# control_board.net
KiCad netlist of a schematic drawn in EAGLE
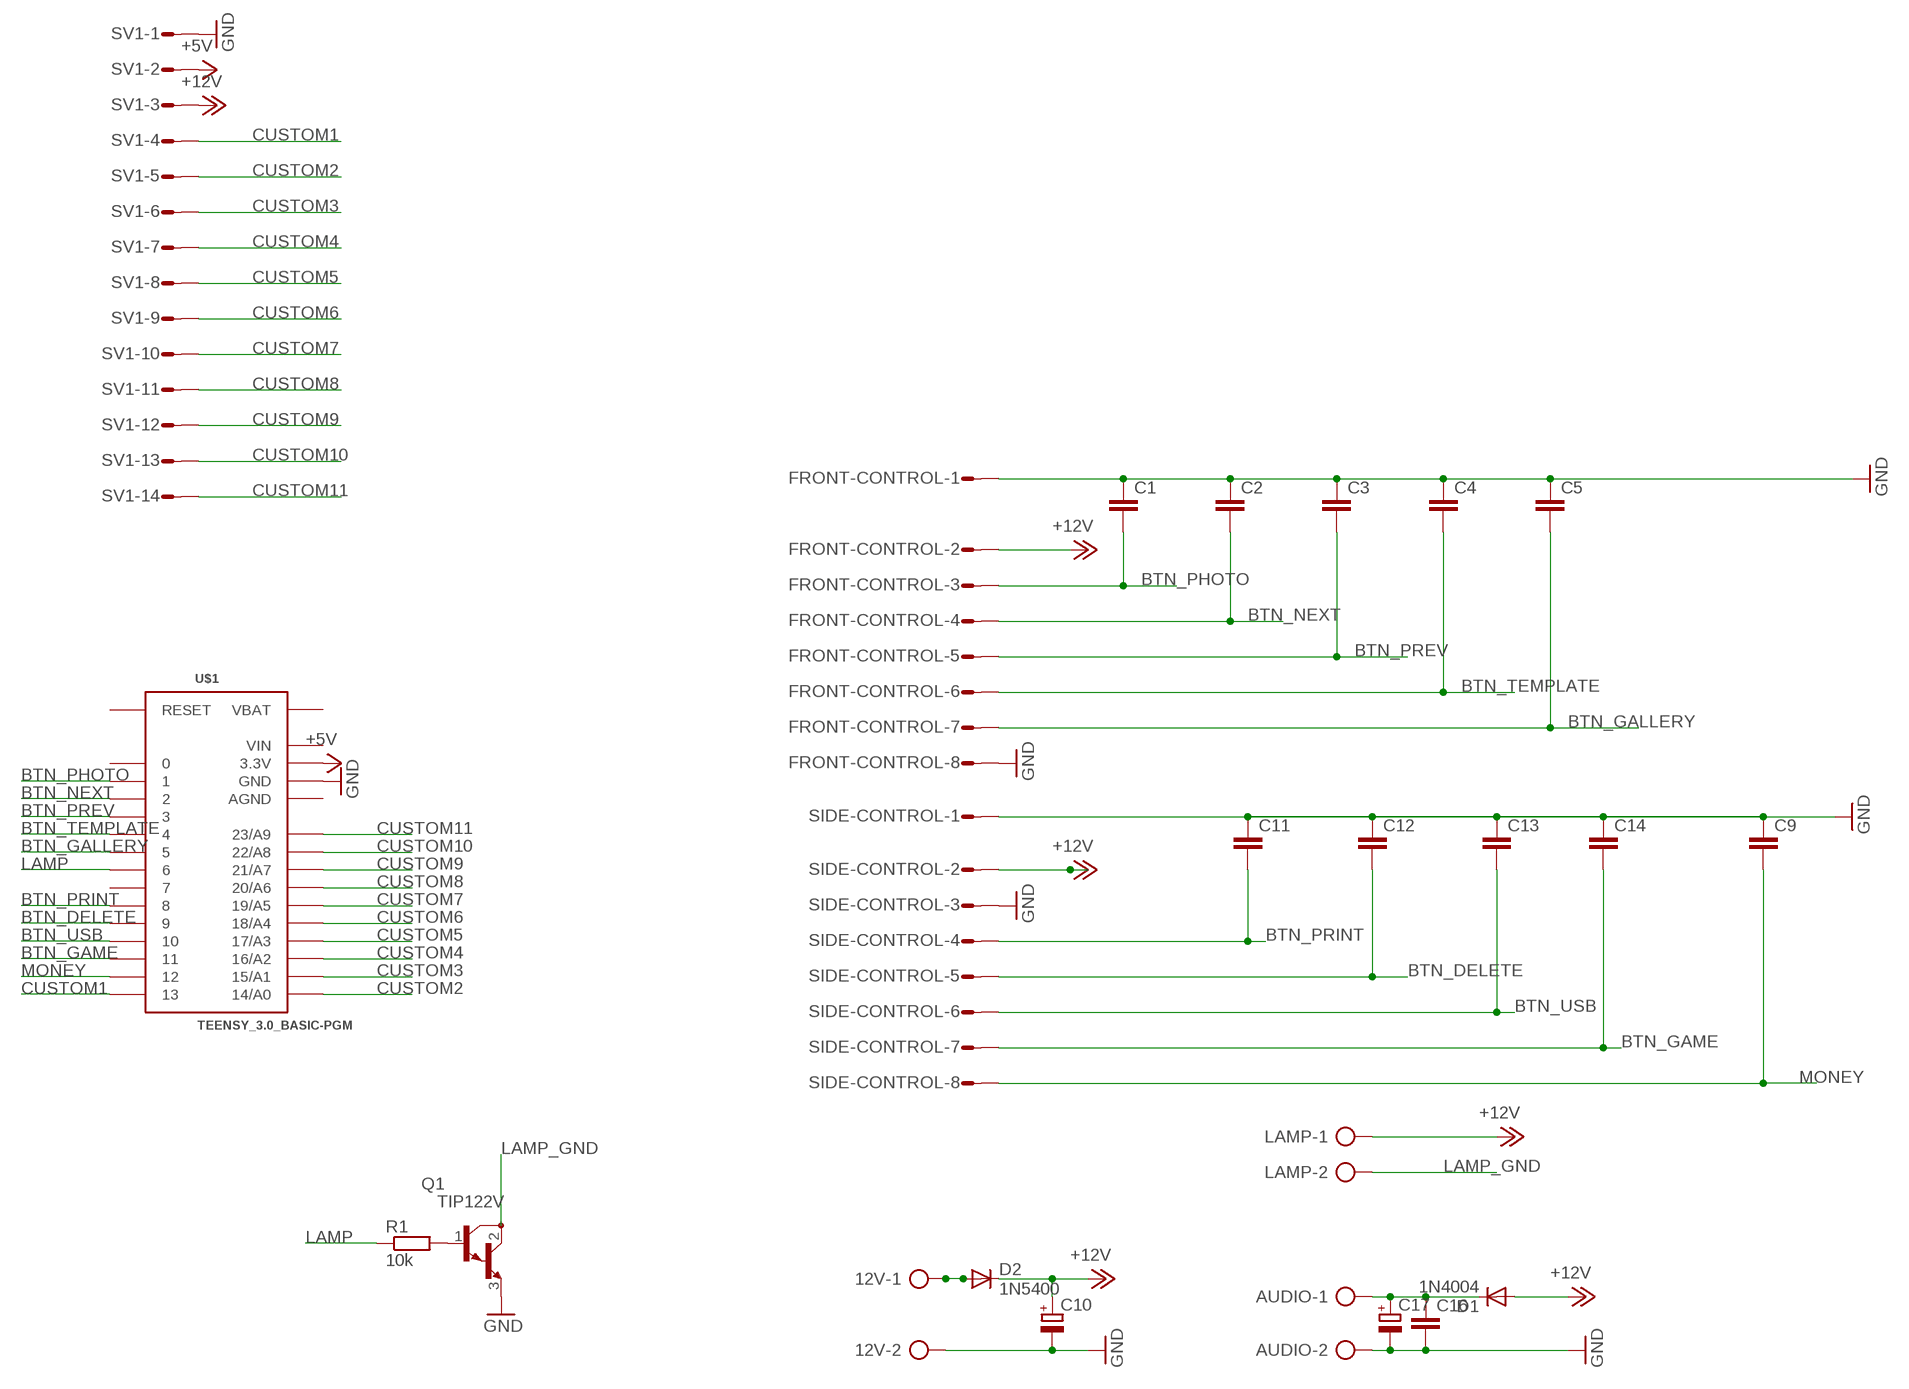
[diagram p0: schematic, sheet 1]

(export (version "E")
  (design (tool "Eeschema 10.0.6"))
  (components
    (comp (ref "12V")
      (value "AK300/2")
      (footprint "eagle-import:AK300_2")
      (libsource (lib "eagle-import") (part "AK300/2"))
    )
    (comp (ref "AUDIO")
      (value "AK300/2")
      (footprint "eagle-import:AK300_2")
      (libsource (lib "eagle-import") (part "AK300/2"))
    )
    (comp (ref "C1")
      (value "C-EU025-025X050")
      (footprint "eagle-import:C025-025X050")
      (libsource (lib "eagle-import") (part "resistor_C-EU025-025X050"))
    )
    (comp (ref "C2")
      (value "C-EU025-025X050")
      (footprint "eagle-import:C025-025X050")
      (libsource (lib "eagle-import") (part "resistor_C-EU025-025X050"))
    )
    (comp (ref "C3")
      (value "C-EU025-025X050")
      (footprint "eagle-import:C025-025X050")
      (libsource (lib "eagle-import") (part "resistor_C-EU025-025X050"))
    )
    (comp (ref "C4")
      (value "C-EU025-025X050")
      (footprint "eagle-import:C025-025X050")
      (libsource (lib "eagle-import") (part "resistor_C-EU025-025X050"))
    )
    (comp (ref "C5")
      (value "C-EU025-025X050")
      (footprint "eagle-import:C025-025X050")
      (libsource (lib "eagle-import") (part "resistor_C-EU025-025X050"))
    )
    (comp (ref "C9")
      (value "C-EU025-025X050")
      (footprint "eagle-import:C025-025X050")
      (libsource (lib "eagle-import") (part "C-EU025-025X050"))
    )
    (comp (ref "C10")
      (value "CPOL-EUE5-8.5")
      (footprint "eagle-import:E5-8,5")
      (libsource (lib "eagle-import") (part "CPOL-EUE5-8.5"))
    )
    (comp (ref "C11")
      (value "C-EU025-025X050")
      (footprint "eagle-import:C025-025X050")
      (libsource (lib "eagle-import") (part "C-EU025-025X050"))
    )
    (comp (ref "C12")
      (value "C-EU025-025X050")
      (footprint "eagle-import:C025-025X050")
      (libsource (lib "eagle-import") (part "C-EU025-025X050"))
    )
    (comp (ref "C13")
      (value "C-EU025-025X050")
      (footprint "eagle-import:C025-025X050")
      (libsource (lib "eagle-import") (part "C-EU025-025X050"))
    )
    (comp (ref "C14")
      (value "C-EU025-025X050")
      (footprint "eagle-import:C025-025X050")
      (libsource (lib "eagle-import") (part "C-EU025-025X050"))
    )
    (comp (ref "C16")
      (value "C-EU025-025X050")
      (footprint "eagle-import:C025-025X050")
      (libsource (lib "eagle-import") (part "C-EU025-025X050"))
    )
    (comp (ref "C17")
      (value "CPOL-EUE5-5")
      (footprint "eagle-import:E5-5")
      (libsource (lib "eagle-import") (part "CPOL-EUE5-5"))
    )
    (comp (ref "D1")
      (value "1N4004")
      (footprint "eagle-import:DO41-10")
      (libsource (lib "eagle-import") (part "1N4004"))
    )
    (comp (ref "D2")
      (value "1N5400")
      (footprint "eagle-import:DO201-15")
      (libsource (lib "eagle-import") (part "1N5400"))
    )
    (comp (ref "FRONT-CONTROL")
      (value "S08P")
      (footprint "eagle-import:S08P")
      (libsource (lib "eagle-import") (part "S08P"))
    )
    (comp (ref "LAMP")
      (value "AK300/2")
      (footprint "eagle-import:AK300_2")
      (libsource (lib "eagle-import") (part "AK300/2"))
    )
    (comp (ref "Q1")
      (value "TIP122V")
      (footprint "eagle-import:TO220V")
      (libsource (lib "eagle-import") (part "TIP122V"))
    )
    (comp (ref "R1")
      (value "10k")
      (footprint "eagle-import:0204_7")
      (libsource (lib "eagle-import") (part "R-EU_0204/7"))
    )
    (comp (ref "SIDE-CONTROL")
      (value "S08P")
      (footprint "eagle-import:S08P")
      (libsource (lib "eagle-import") (part "S08P"))
    )
    (comp (ref "SV1")
      (value "S14P")
      (footprint "eagle-import:S14P")
      (libsource (lib "eagle-import") (part "S14P"))
    )
    (comp (ref "U$1")
      (value "TEENSY_3.0_BASIC-PGM")
      (footprint "eagle-import:TEENSY_3.0_BASIC-PGM")
      (libsource (lib "eagle-import") (part "TEENSY_3.0_BASIC-PGM"))
    )
  )
  (nets
    (net (code "1") (name "+5V") (class "Default")
      (node (ref "SV1") (pin "2") (pinfunction "S_2") (pintype "passive"))
      (node (ref "U$1") (pin "3.3V") (pinfunction "3.3V_3.3V") (pintype "power_in"))
      (node (ref "U$1") (pin "3.3V1") (pinfunction "3.3V_3.3V1") (pintype "power_in"))
    )
    (net (code "2") (name "+12V") (class "Default")
      (node (ref "C10") (pin "+") (pinfunction "+_+") (pintype "passive"))
      (node (ref "D1") (pin "A") (pinfunction "A_A") (pintype "passive"))
      (node (ref "D2") (pin "C") (pinfunction "C_C") (pintype "passive"))
      (node (ref "FRONT-CONTROL") (pin "2") (pinfunction "S_2") (pintype "passive"))
      (node (ref "LAMP") (pin "1") (pinfunction "KL_1") (pintype "passive"))
      (node (ref "SIDE-CONTROL") (pin "2") (pinfunction "S_2") (pintype "passive"))
      (node (ref "SV1") (pin "3") (pinfunction "S_3") (pintype "passive"))
    )
    (net (code "3") (name "/AGND") (class "Default")
      (node (ref "U$1") (pin "AGND") (pinfunction "AGND_AGND") (pintype "power_in"))
    )
    (net (code "4") (name "/BTN_DELETE") (class "Default")
      (node (ref "C12") (pin "2") (pinfunction "2_2") (pintype "passive"))
      (node (ref "SIDE-CONTROL") (pin "5") (pinfunction "S_5") (pintype "passive"))
      (node (ref "U$1") (pin "9") (pinfunction "9_9") (pintype "bidirectional"))
    )
    (net (code "5") (name "/BTN_GALLERY") (class "Default")
      (node (ref "C5") (pin "2") (pinfunction "2_2") (pintype "passive"))
      (node (ref "FRONT-CONTROL") (pin "7") (pinfunction "S_7") (pintype "passive"))
      (node (ref "U$1") (pin "5") (pinfunction "5_5") (pintype "bidirectional"))
    )
    (net (code "6") (name "/BTN_GAME") (class "Default")
      (node (ref "C14") (pin "2") (pinfunction "2_2") (pintype "passive"))
      (node (ref "SIDE-CONTROL") (pin "7") (pinfunction "S_7") (pintype "passive"))
      (node (ref "U$1") (pin "11") (pinfunction "11_11") (pintype "bidirectional"))
    )
    (net (code "7") (name "/BTN_NEXT") (class "Default")
      (node (ref "C2") (pin "2") (pinfunction "2_2") (pintype "passive"))
      (node (ref "FRONT-CONTROL") (pin "4") (pinfunction "S_4") (pintype "passive"))
      (node (ref "U$1") (pin "2") (pinfunction "2_2") (pintype "bidirectional"))
    )
    (net (code "8") (name "/BTN_PHOTO") (class "Default")
      (node (ref "C1") (pin "2") (pinfunction "2_2") (pintype "passive"))
      (node (ref "FRONT-CONTROL") (pin "3") (pinfunction "S_3") (pintype "passive"))
      (node (ref "U$1") (pin "1") (pinfunction "1_1") (pintype "bidirectional"))
    )
    (net (code "9") (name "/BTN_PREV") (class "Default")
      (node (ref "C3") (pin "2") (pinfunction "2_2") (pintype "passive"))
      (node (ref "FRONT-CONTROL") (pin "5") (pinfunction "S_5") (pintype "passive"))
      (node (ref "U$1") (pin "3") (pinfunction "3_3") (pintype "bidirectional"))
    )
    (net (code "10") (name "/BTN_PRINT") (class "Default")
      (node (ref "C11") (pin "2") (pinfunction "2_2") (pintype "passive"))
      (node (ref "SIDE-CONTROL") (pin "4") (pinfunction "S_4") (pintype "passive"))
      (node (ref "U$1") (pin "8") (pinfunction "8_8") (pintype "bidirectional"))
    )
    (net (code "11") (name "/BTN_TEMPLATE") (class "Default")
      (node (ref "C4") (pin "2") (pinfunction "2_2") (pintype "passive"))
      (node (ref "FRONT-CONTROL") (pin "6") (pinfunction "S_6") (pintype "passive"))
      (node (ref "U$1") (pin "4") (pinfunction "4_4") (pintype "bidirectional"))
    )
    (net (code "12") (name "/BTN_USB") (class "Default")
      (node (ref "C13") (pin "2") (pinfunction "2_2") (pintype "passive"))
      (node (ref "SIDE-CONTROL") (pin "6") (pinfunction "S_6") (pintype "passive"))
      (node (ref "U$1") (pin "10") (pinfunction "10_10") (pintype "bidirectional"))
    )
    (net (code "13") (name "/CUSTOM1") (class "Default")
      (node (ref "SV1") (pin "4") (pinfunction "S_4") (pintype "passive"))
      (node (ref "U$1") (pin "13") (pinfunction "13_13") (pintype "bidirectional"))
    )
    (net (code "14") (name "/CUSTOM2") (class "Default")
      (node (ref "SV1") (pin "5") (pinfunction "S_5") (pintype "passive"))
      (node (ref "U$1") (pin "14/A0") (pinfunction "14/A0_14/A0") (pintype "bidirectional"))
    )
    (net (code "15") (name "/CUSTOM3") (class "Default")
      (node (ref "SV1") (pin "6") (pinfunction "S_6") (pintype "passive"))
      (node (ref "U$1") (pin "15/A1") (pinfunction "15/A1_15/A1") (pintype "bidirectional"))
    )
    (net (code "16") (name "/CUSTOM4") (class "Default")
      (node (ref "SV1") (pin "7") (pinfunction "S_7") (pintype "passive"))
      (node (ref "U$1") (pin "16/A2") (pinfunction "16/A2_16/A2") (pintype "bidirectional"))
    )
    (net (code "17") (name "/CUSTOM5") (class "Default")
      (node (ref "SV1") (pin "8") (pinfunction "S_8") (pintype "passive"))
      (node (ref "U$1") (pin "17/A3") (pinfunction "17/A3_17/A3") (pintype "bidirectional"))
    )
    (net (code "18") (name "/CUSTOM6") (class "Default")
      (node (ref "SV1") (pin "9") (pinfunction "S_9") (pintype "passive"))
      (node (ref "U$1") (pin "18/A4") (pinfunction "18/A4_18/A4") (pintype "bidirectional"))
    )
    (net (code "19") (name "/CUSTOM7") (class "Default")
      (node (ref "SV1") (pin "10") (pinfunction "S_10") (pintype "passive"))
      (node (ref "U$1") (pin "19/A5") (pinfunction "19/A5_19/A5") (pintype "bidirectional"))
    )
    (net (code "20") (name "/CUSTOM8") (class "Default")
      (node (ref "SV1") (pin "11") (pinfunction "S_11") (pintype "passive"))
      (node (ref "U$1") (pin "20/A6") (pinfunction "20/A6_20/A6") (pintype "bidirectional"))
    )
    (net (code "21") (name "/CUSTOM9") (class "Default")
      (node (ref "SV1") (pin "12") (pinfunction "S_12") (pintype "passive"))
      (node (ref "U$1") (pin "21/A7") (pinfunction "21/A7_21/A7") (pintype "bidirectional"))
    )
    (net (code "22") (name "/CUSTOM10") (class "Default")
      (node (ref "SV1") (pin "13") (pinfunction "S_13") (pintype "passive"))
      (node (ref "U$1") (pin "22/A8") (pinfunction "22/A8_22/A8") (pintype "bidirectional"))
    )
    (net (code "23") (name "/CUSTOM11") (class "Default")
      (node (ref "SV1") (pin "14") (pinfunction "S_14") (pintype "passive"))
      (node (ref "U$1") (pin "23/A9") (pinfunction "23/A9_23/A9") (pintype "bidirectional"))
    )
    (net (code "24") (name "/LAMP") (class "Default")
      (node (ref "R1") (pin "1") (pinfunction "1_1") (pintype "passive"))
      (node (ref "U$1") (pin "6") (pinfunction "6_6") (pintype "bidirectional"))
    )
    (net (code "25") (name "/LAMP_GND") (class "Default")
      (node (ref "LAMP") (pin "2") (pinfunction "KL_2") (pintype "passive"))
      (node (ref "Q1") (pin "2") (pinfunction "C_2") (pintype "passive"))
    )
    (net (code "26") (name "/MONEY") (class "Default")
      (node (ref "C9") (pin "2") (pinfunction "2_2") (pintype "passive"))
      (node (ref "SIDE-CONTROL") (pin "8") (pinfunction "S_8") (pintype "passive"))
      (node (ref "U$1") (pin "12") (pinfunction "12_12") (pintype "bidirectional"))
    )
    (net (code "27") (name "/VBAT") (class "Default")
      (node (ref "U$1") (pin "VBAT") (pinfunction "VBAT_VBAT") (pintype "power_in"))
    )
    (net (code "28") (name "/VIN") (class "Default")
      (node (ref "U$1") (pin "VIN") (pinfunction "VIN_VIN") (pintype "power_in"))
    )
    (net (code "29") (name "GND") (class "Default")
      (node (ref "12V") (pin "2") (pinfunction "KL_2") (pintype "passive"))
      (node (ref "AUDIO") (pin "2") (pinfunction "KL_2") (pintype "passive"))
      (node (ref "C1") (pin "1") (pinfunction "1_1") (pintype "passive"))
      (node (ref "C10") (pin "-") (pinfunction "-_-") (pintype "passive"))
      (node (ref "C11") (pin "1") (pinfunction "1_1") (pintype "passive"))
      (node (ref "C12") (pin "1") (pinfunction "1_1") (pintype "passive"))
      (node (ref "C13") (pin "1") (pinfunction "1_1") (pintype "passive"))
      (node (ref "C14") (pin "1") (pinfunction "1_1") (pintype "passive"))
      (node (ref "C16") (pin "2") (pinfunction "2_2") (pintype "passive"))
      (node (ref "C17") (pin "-") (pinfunction "-_-") (pintype "passive"))
      (node (ref "C2") (pin "1") (pinfunction "1_1") (pintype "passive"))
      (node (ref "C3") (pin "1") (pinfunction "1_1") (pintype "passive"))
      (node (ref "C4") (pin "1") (pinfunction "1_1") (pintype "passive"))
      (node (ref "C5") (pin "1") (pinfunction "1_1") (pintype "passive"))
      (node (ref "C9") (pin "1") (pinfunction "1_1") (pintype "passive"))
      (node (ref "FRONT-CONTROL") (pin "1") (pinfunction "S_1") (pintype "passive"))
      (node (ref "FRONT-CONTROL") (pin "8") (pinfunction "S_8") (pintype "passive"))
      (node (ref "Q1") (pin "3") (pinfunction "E_3") (pintype "passive"))
      (node (ref "SIDE-CONTROL") (pin "1") (pinfunction "S_1") (pintype "passive"))
      (node (ref "SIDE-CONTROL") (pin "3") (pinfunction "S_3") (pintype "passive"))
      (node (ref "SV1") (pin "1") (pinfunction "S_1") (pintype "passive"))
      (node (ref "U$1") (pin "GND") (pinfunction "GND_GND") (pintype "power_in"))
      (node (ref "U$1") (pin "GND1") (pinfunction "GND_GND1") (pintype "power_in"))
    )
    (net (code "30") (name "Net-(12VA-KL)") (class "Default")
      (node (ref "12V") (pin "1") (pinfunction "KL_1") (pintype "passive"))
      (node (ref "D2") (pin "A") (pinfunction "A_A") (pintype "passive"))
    )
    (net (code "31") (name "Net-(AUDIOA-KL)") (class "Default")
      (node (ref "AUDIO") (pin "1") (pinfunction "KL_1") (pintype "passive"))
      (node (ref "C16") (pin "1") (pinfunction "1_1") (pintype "passive"))
      (node (ref "C17") (pin "+") (pinfunction "+_+") (pintype "passive"))
      (node (ref "D1") (pin "C") (pinfunction "C_C") (pintype "passive"))
    )
    (net (code "32") (name "Net-(Q1-B)") (class "Default")
      (node (ref "Q1") (pin "1") (pinfunction "B_1") (pintype "passive"))
      (node (ref "R1") (pin "2") (pinfunction "2_2") (pintype "passive"))
    )
    (net (code "33") (name "unconnected-(U$1-Pad0)") (class "Default")
      (node (ref "U$1") (pin "0") (pinfunction "0_0") (pintype "bidirectional"))
    )
    (net (code "34") (name "unconnected-(U$1-Pad7)") (class "Default")
      (node (ref "U$1") (pin "7") (pinfunction "7_7") (pintype "bidirectional"))
    )
    (net (code "35") (name "unconnected-(U$1-PadRESET)") (class "Default")
      (node (ref "U$1") (pin "RESET") (pinfunction "RESET_RESET") (pintype "bidirectional"))
    )
  )
)
